# separation.net
KiCad netlist of a schematic drawn in EAGLE
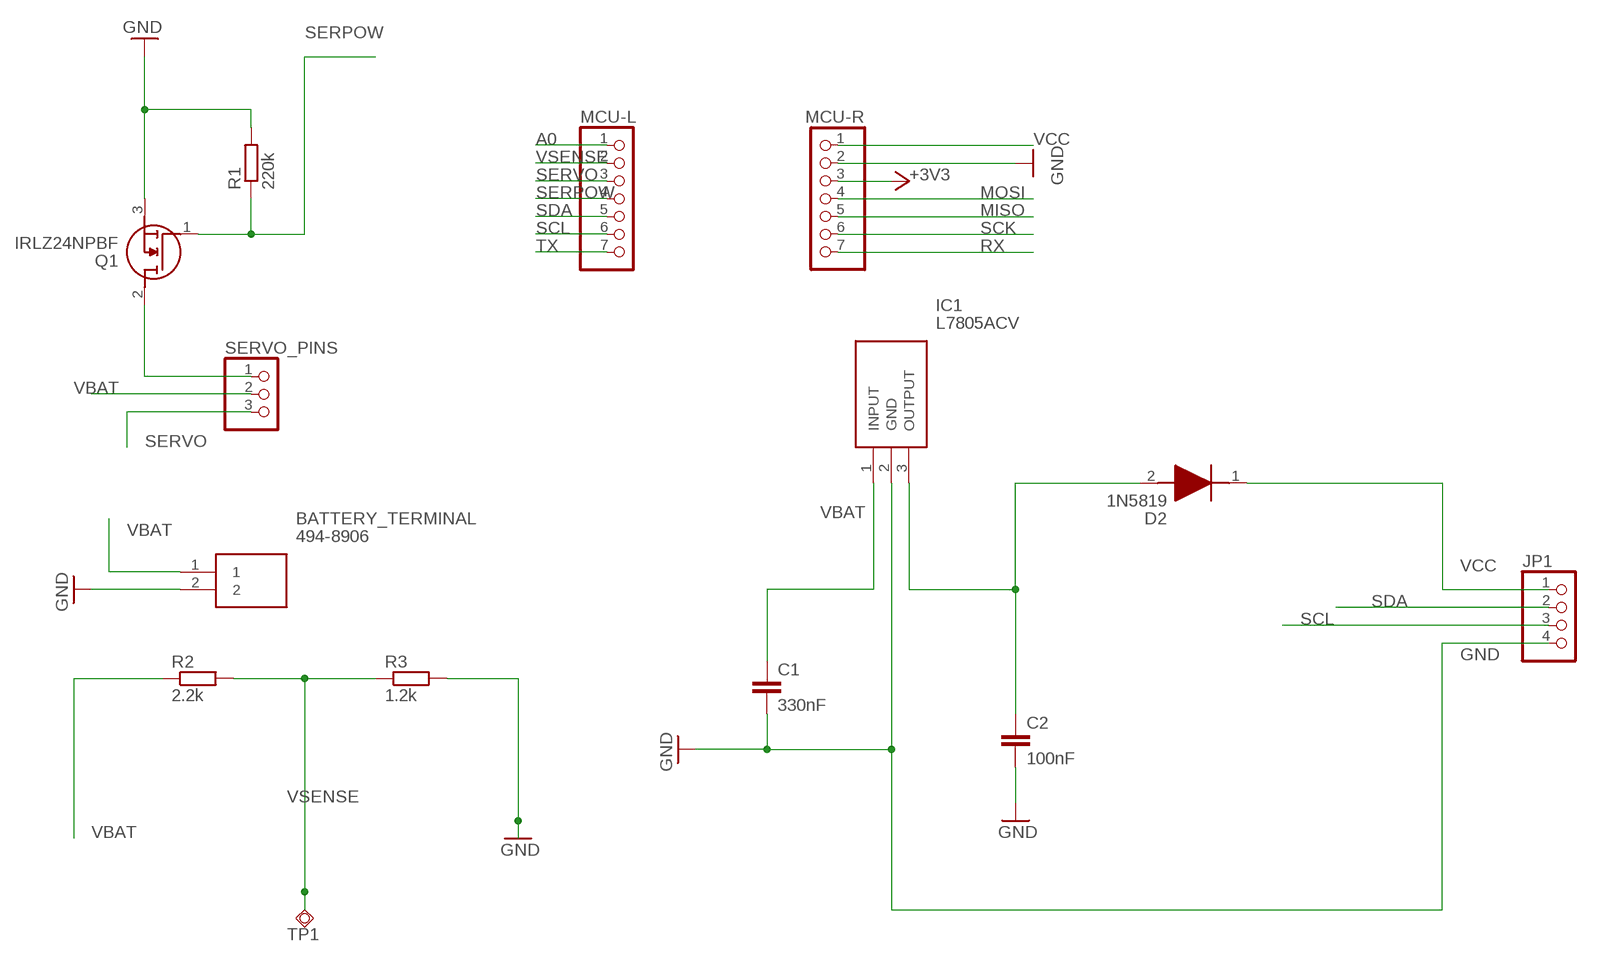
[diagram p0: schematic, sheet 1]

(export (version "E")
  (design (tool "Eeschema 10.0.6"))
  (components
    (comp (ref "BATTERY_TERMINAL")
      (value "494-8906")
      (footprint "eagle-import:SHDR2W100P0X500_1X2_1000X750X1")
      (libsource (lib "eagle-import") (part "494-8906"))
    )
    (comp (ref "C1")
      (value "330nF")
      (footprint "eagle-import:C2.5-3")
      (libsource (lib "eagle-import") (part "C2,5-3"))
    )
    (comp (ref "C2")
      (value "100nF")
      (footprint "eagle-import:C2.5-3")
      (libsource (lib "eagle-import") (part "C2,5-3"))
    )
    (comp (ref "D2")
      (value "1N5819")
      (footprint "eagle-import:DIOAD1414W86L464D238")
      (fields (field (name "RS_PART_NUMBER") "4864460P"))
      (libsource (lib "eagle-import") (part "1N5819"))
    )
    (comp (ref "IC1")
      (value "L7805ACV")
      (footprint "eagle-import:TO255P460X1020X2008-3P")
      (fields (field (name "RS_PART_NUMBER") "2988508P"))
      (libsource (lib "eagle-import") (part "L7805ACV"))
    )
    (comp (ref "JP1")
      (value "PINHD-1X4")
      (footprint "eagle-import:1X04")
      (libsource (lib "eagle-import") (part "PINHD-1X4"))
    )
    (comp (ref "MCU-L")
      (value "PINHD-1X7")
      (footprint "eagle-import:1X07")
      (libsource (lib "eagle-import") (part "PINHD-1X7"))
    )
    (comp (ref "MCU-R")
      (value "PINHD-1X7")
      (footprint "eagle-import:1X07")
      (libsource (lib "eagle-import") (part "PINHD-1X7"))
    )
    (comp (ref "Q1")
      (value "IRLZ24NPBF")
      (footprint "eagle-import:TO254P469X1042X1967-3P")
      (fields (field (name "RS_PART_NUMBER") "5411231P"))
      (libsource (lib "eagle-import") (part "IRLZ24NPBF"))
    )
    (comp (ref "R1")
      (value "220k")
      (footprint "eagle-import:0204_7")
      (libsource (lib "eagle-import") (part "R-EU_0204/7"))
    )
    (comp (ref "R2")
      (value "2.2k")
      (footprint "eagle-import:0204_7")
      (libsource (lib "eagle-import") (part "R-EU_0204/7"))
    )
    (comp (ref "R3")
      (value "1.2k")
      (footprint "eagle-import:0204_7")
      (libsource (lib "eagle-import") (part "R-EU_0204/7"))
    )
    (comp (ref "SERVO_PINS")
      (value "PINHD-1X3")
      (footprint "eagle-import:1X03")
      (libsource (lib "eagle-import") (part "PINHD-1X3"))
    )
    (comp (ref "TP1")
      (value "TPSQB1,27")
      (footprint "eagle-import:B1,27")
      (libsource (lib "eagle-import") (part "TPSQB1,27"))
    )
  )
  (nets
    (net (code "1") (name "+3V3") (class "Default")
      (node (ref "MCU-R") (pin "3") (pinfunction "3_3") (pintype "passive"))
    )
    (net (code "2") (name "/A0") (class "Default")
      (node (ref "MCU-L") (pin "1") (pinfunction "1_1") (pintype "passive"))
    )
    (net (code "3") (name "/MISO") (class "Default")
      (node (ref "MCU-R") (pin "5") (pinfunction "5_5") (pintype "passive"))
    )
    (net (code "4") (name "/MOSI") (class "Default")
      (node (ref "MCU-R") (pin "4") (pinfunction "4_4") (pintype "passive"))
    )
    (net (code "5") (name "/RX") (class "Default")
      (node (ref "MCU-R") (pin "7") (pinfunction "7_7") (pintype "passive"))
    )
    (net (code "6") (name "/SCK") (class "Default")
      (node (ref "MCU-R") (pin "6") (pinfunction "6_6") (pintype "passive"))
    )
    (net (code "7") (name "/SCL") (class "Default")
      (node (ref "JP1") (pin "3") (pinfunction "3_3") (pintype "passive"))
      (node (ref "MCU-L") (pin "6") (pinfunction "6_6") (pintype "passive"))
    )
    (net (code "8") (name "/SDA") (class "Default")
      (node (ref "JP1") (pin "2") (pinfunction "2_2") (pintype "passive"))
      (node (ref "MCU-L") (pin "5") (pinfunction "5_5") (pintype "passive"))
    )
    (net (code "9") (name "/SERPOW") (class "Default")
      (node (ref "MCU-L") (pin "4") (pinfunction "4_4") (pintype "passive"))
      (node (ref "Q1") (pin "1") (pinfunction "G_1") (pintype "bidirectional"))
      (node (ref "R1") (pin "1") (pinfunction "1_1") (pintype "passive"))
    )
    (net (code "10") (name "/SERVO") (class "Default")
      (node (ref "MCU-L") (pin "3") (pinfunction "3_3") (pintype "passive"))
      (node (ref "SERVO_PINS") (pin "3") (pinfunction "3_3") (pintype "passive"))
    )
    (net (code "11") (name "/TX") (class "Default")
      (node (ref "MCU-L") (pin "7") (pinfunction "7_7") (pintype "passive"))
    )
    (net (code "12") (name "/VBAT") (class "Default")
      (node (ref "BATTERY_TERMINAL") (pin "1") (pinfunction "1_1") (pintype "bidirectional"))
      (node (ref "C1") (pin "1") (pinfunction "1_1") (pintype "passive"))
      (node (ref "IC1") (pin "1") (pinfunction "INPUT_1") (pintype "bidirectional"))
      (node (ref "R2") (pin "1") (pinfunction "1_1") (pintype "passive"))
      (node (ref "SERVO_PINS") (pin "2") (pinfunction "2_2") (pintype "passive"))
    )
    (net (code "13") (name "/VCC") (class "Default")
      (node (ref "D2") (pin "1") (pinfunction "K_1") (pintype "bidirectional"))
      (node (ref "JP1") (pin "1") (pinfunction "1_1") (pintype "passive"))
      (node (ref "MCU-R") (pin "1") (pinfunction "1_1") (pintype "passive"))
    )
    (net (code "14") (name "/VSENSE") (class "Default")
      (node (ref "MCU-L") (pin "2") (pinfunction "2_2") (pintype "passive"))
      (node (ref "R2") (pin "2") (pinfunction "2_2") (pintype "passive"))
      (node (ref "R3") (pin "1") (pinfunction "1_1") (pintype "passive"))
      (node (ref "TP1") (pin "TP") (pinfunction "TP_TP") (pintype "input"))
    )
    (net (code "15") (name "GND") (class "Default")
      (node (ref "BATTERY_TERMINAL") (pin "2") (pinfunction "2_2") (pintype "bidirectional"))
      (node (ref "C1") (pin "2") (pinfunction "2_2") (pintype "passive"))
      (node (ref "C2") (pin "2") (pinfunction "2_2") (pintype "passive"))
      (node (ref "IC1") (pin "2") (pinfunction "GND_2") (pintype "bidirectional"))
      (node (ref "JP1") (pin "4") (pinfunction "4_4") (pintype "passive"))
      (node (ref "MCU-R") (pin "2") (pinfunction "2_2") (pintype "passive"))
      (node (ref "Q1") (pin "3") (pinfunction "S_3") (pintype "bidirectional"))
      (node (ref "R1") (pin "2") (pinfunction "2_2") (pintype "passive"))
      (node (ref "R3") (pin "2") (pinfunction "2_2") (pintype "passive"))
    )
    (net (code "16") (name "Net-(D2-A)") (class "Default")
      (node (ref "C2") (pin "1") (pinfunction "1_1") (pintype "passive"))
      (node (ref "D2") (pin "2") (pinfunction "A_2") (pintype "bidirectional"))
      (node (ref "IC1") (pin "3") (pinfunction "OUTPUT_3") (pintype "bidirectional"))
    )
    (net (code "17") (name "Net-(Q1-D)") (class "Default")
      (node (ref "Q1") (pin "2") (pinfunction "D_2") (pintype "bidirectional"))
      (node (ref "SERVO_PINS") (pin "1") (pinfunction "1_1") (pintype "passive"))
    )
  )
)
